# USB_HUB.net
KiCad netlist of a schematic drawn in Altium Designer
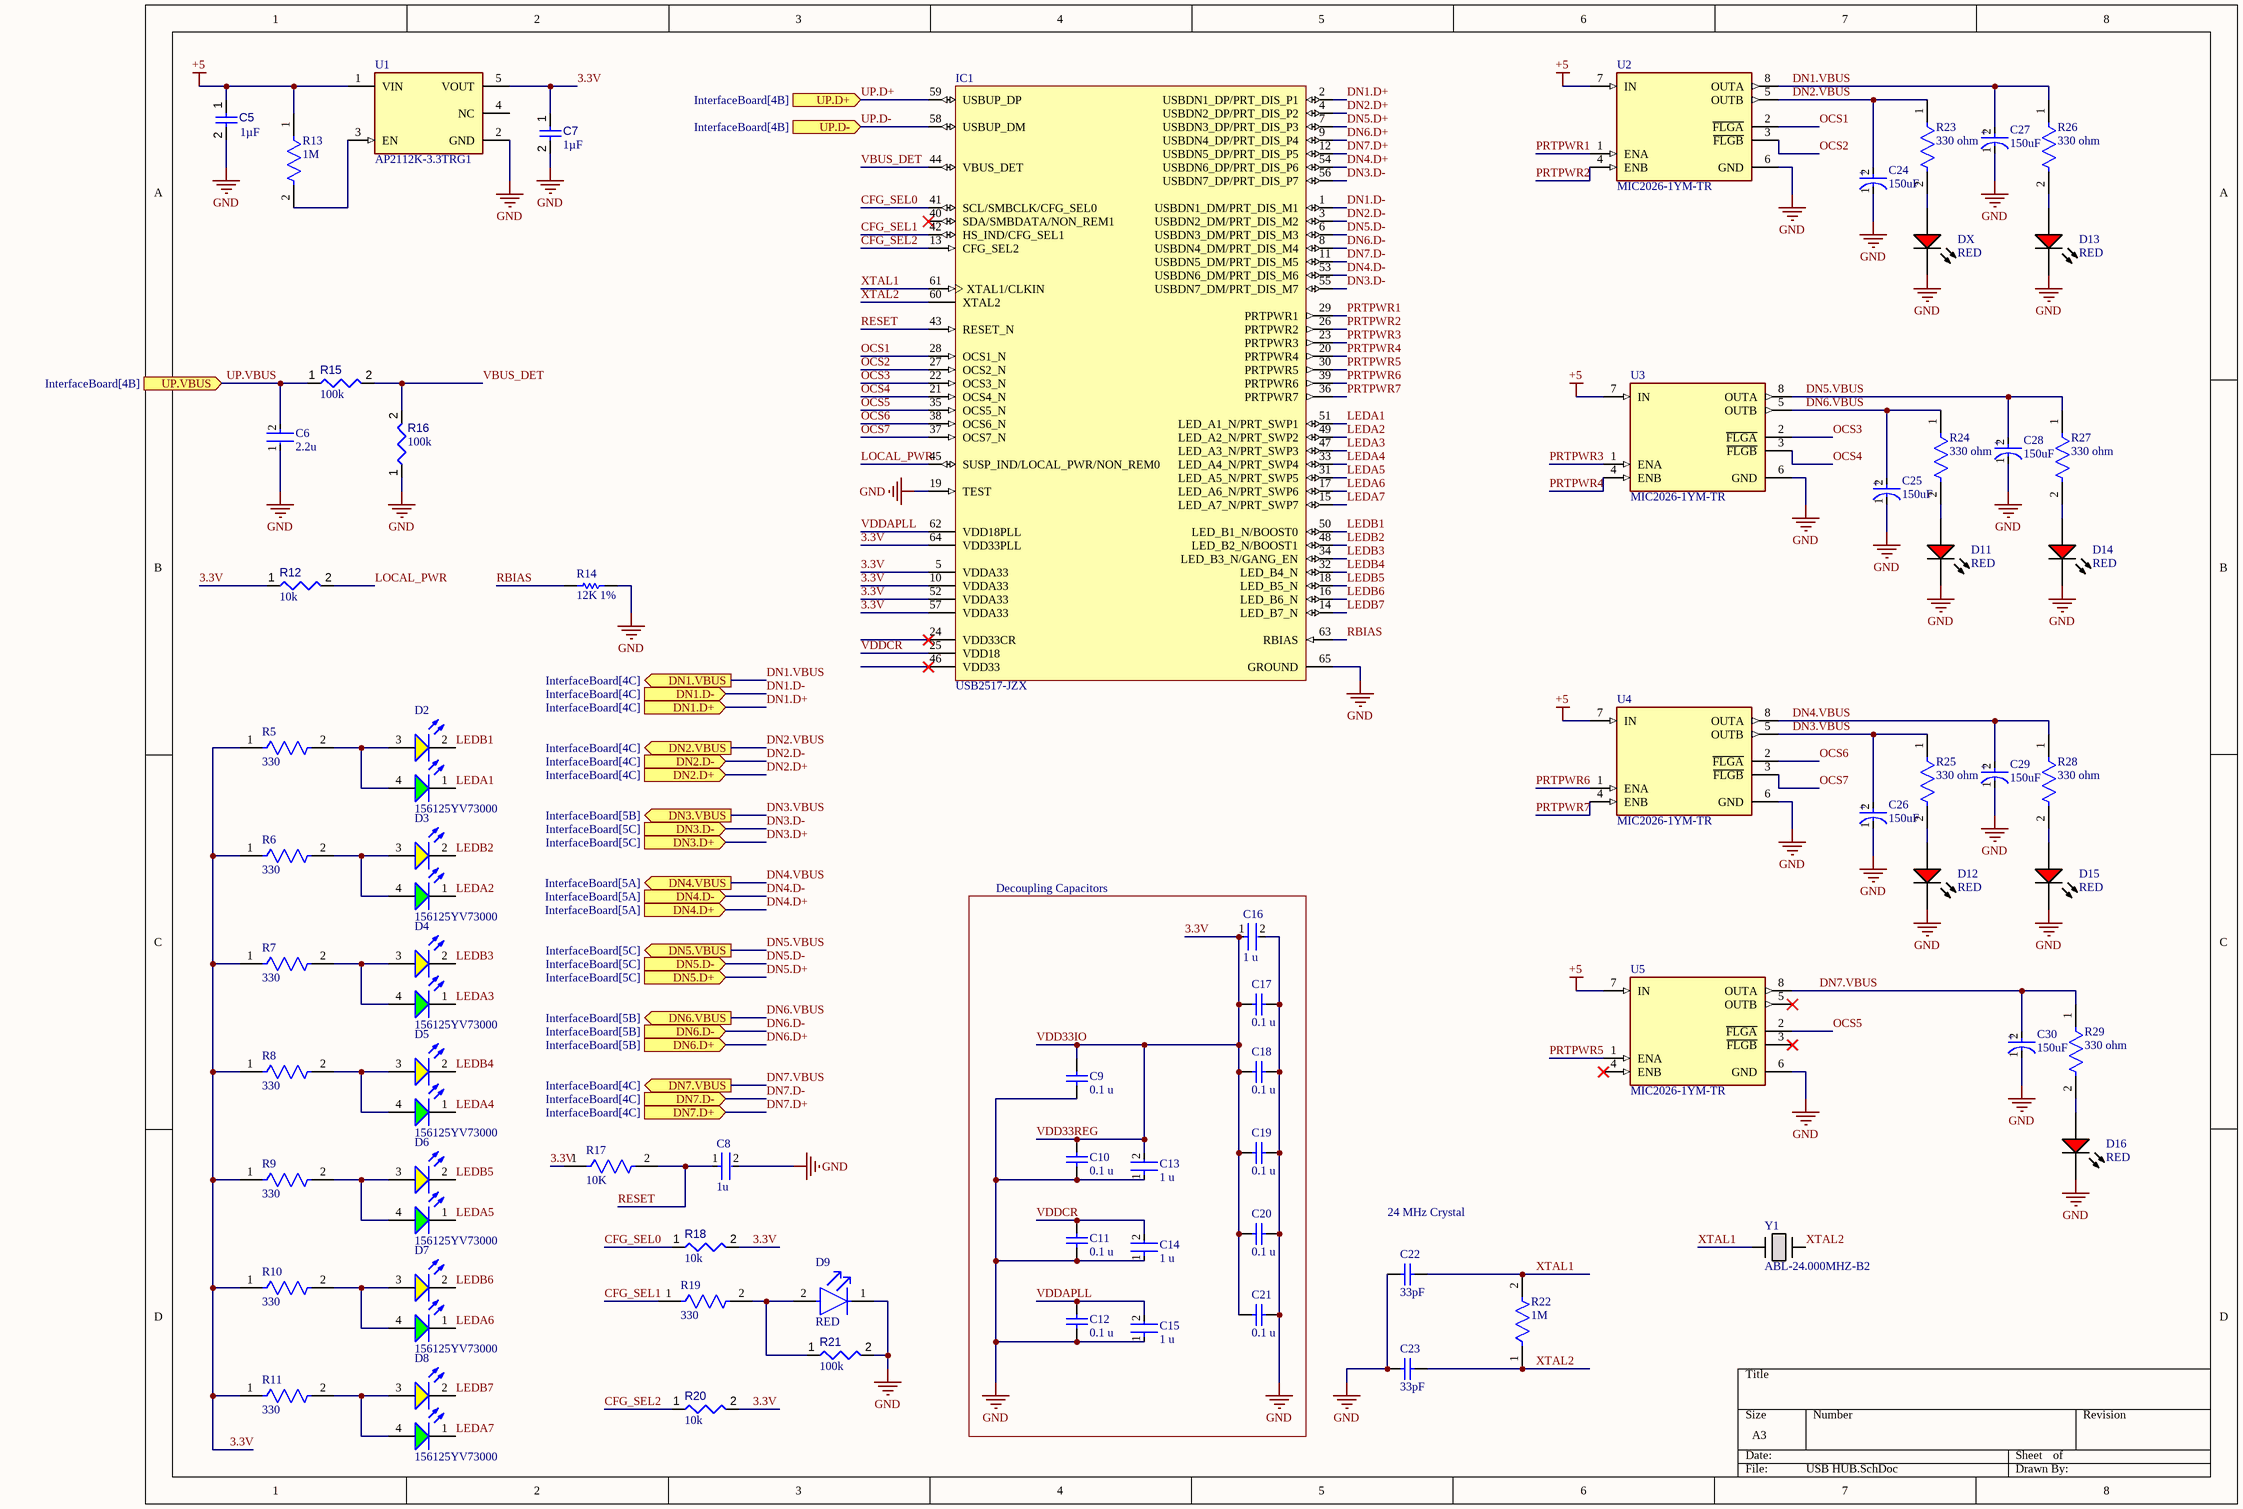
[diagram p0: USB HUB.SchDoc]

(export (version "E")
  (design (tool "Eeschema 10.0.6"))
  (components
    (comp (ref "C5")
      (value "1µF")
      (footprint "CAPC1608X94X35NL15T15")
      (description "Chip Capacitor, 1 uF, +/- 10%, 16 V, 0603 (1608 Metric)")
      (fields (field (name "TOLERANCE") "10%") (field (name "Comment") "Capacitor 1 uF +/- 10% 16 V 0603"))
      (libsource (lib "Isaac Lee Altium Cloud") (part "CAP-NP-2"))
    )
    (comp (ref "C6")
      (value "2.2u")
      (footprint "FP-C1608-080-0_1-MFG")
      (description "Multilayer Ceramic Capacitors 2.2μF ±10% 25V X5R SMD 0603")
      (fields (field (name "TOLERANCE") "10%"))
      (libsource (lib "Altium Content Vault") (part "236180d848d6139a670b325ea6854c9"))
    )
    (comp (ref "C7")
      (value "1µF")
      (footprint "CAPC1608X94X35NL15T15")
      (description "Chip Capacitor, 1 uF, +/- 10%, 16 V, 0603 (1608 Metric)")
      (fields (field (name "TOLERANCE") "10%") (field (name "Comment") "Capacitor 1 uF +/- 10% 16 V 0603"))
      (libsource (lib "Isaac Lee Altium Cloud") (part "CAP-NP-2"))
    )
    (comp (ref "C8")
      (value "1u")
      (footprint "FP-0603-L_1_6_0_15-W_0_81-IPC_A")
      (description "General Purpose Ceramic Capacitor, 0603, 1uF, 10%, X5R, 15%, 6.3V")
      (fields (field (name "VOLTAGE") "6.3V") (field (name "TOLERANCE") "10%"))
      (libsource (lib "Altium Content Vault") (part "02cd4be3c70576c341d710602a673aa"))
    )
    (comp (ref "C9")
      (value "0.1 u")
      (footprint "CAPC1608X90X35LL15T15")
      (description "06035C104KAT4A")
      (fields (field (name "MANUFACTURER") "AVX Interconnect / Elco"))
      (libsource (lib "Altium Content Vault") (part "CAP"))
    )
    (comp (ref "C10")
      (value "0.1 u")
      (footprint "CAPC1608X90X35LL15T15")
      (description "06035C104KAT4A")
      (fields (field (name "MANUFACTURER") "AVX Interconnect / Elco"))
      (libsource (lib "Altium Content Vault") (part "CAP"))
    )
    (comp (ref "C11")
      (value "0.1 u")
      (footprint "CAPC1608X90X35LL15T15")
      (description "06035C104KAT4A")
      (fields (field (name "MANUFACTURER") "AVX Interconnect / Elco"))
      (libsource (lib "Altium Content Vault") (part "CAP"))
    )
    (comp (ref "C12")
      (value "0.1 u")
      (footprint "CAPC1608X90X35LL15T15")
      (description "06035C104KAT4A")
      (fields (field (name "MANUFACTURER") "AVX Interconnect / Elco"))
      (libsource (lib "Altium Content Vault") (part "CAP"))
    )
    (comp (ref "C13")
      (value "1 u")
      (footprint "FP-0603-L_1_6_0_15-W_0_8-IPC_C")
      (description "Ceramic Capacitor General Use 1uF ±10% 50V X7R 0603\r\nUMK107AB7105KA-T")
      (fields (field (name "TOLERANCE") "10%"))
      (libsource (lib "Altium Content Vault") (part "11868f565c42a9108669ba33697ecf6"))
    )
    (comp (ref "C14")
      (value "1 u")
      (footprint "FP-0603-L_1_6_0_15-W_0_8-IPC_C")
      (description "Ceramic Capacitor General Use 1uF ±10% 50V X7R 0603\r\nUMK107AB7105KA-T")
      (fields (field (name "TOLERANCE") "10%"))
      (libsource (lib "Altium Content Vault") (part "11868f565c42a9108669ba33697ecf6"))
    )
    (comp (ref "C15")
      (value "1 u")
      (footprint "FP-0603-L_1_6_0_15-W_0_8-IPC_C")
      (description "Ceramic Capacitor General Use 1uF ±10% 50V X7R 0603\r\nUMK107AB7105KA-T")
      (fields (field (name "TOLERANCE") "10%"))
      (libsource (lib "Altium Content Vault") (part "11868f565c42a9108669ba33697ecf6"))
    )
    (comp (ref "C16")
      (value "1 u")
      (footprint "FP-0603-L_1_6_0_15-W_0_8-IPC_C")
      (description "Ceramic Capacitor General Use 1uF ±10% 50V X7R 0603\r\nUMK107AB7105KA-T")
      (fields (field (name "TOLERANCE") "10%"))
      (libsource (lib "Altium Content Vault") (part "11868f565c42a9108669ba33697ecf6"))
    )
    (comp (ref "C17")
      (value "0.1 u")
      (footprint "CAPC1608X90X35LL15T15")
      (description "06035C104KAT4A")
      (fields (field (name "MANUFACTURER") "AVX Interconnect / Elco"))
      (libsource (lib "Altium Content Vault") (part "CAP"))
    )
    (comp (ref "C18")
      (value "0.1 u")
      (footprint "CAPC1608X90X35LL15T15")
      (description "06035C104KAT4A")
      (fields (field (name "MANUFACTURER") "AVX Interconnect / Elco"))
      (libsource (lib "Altium Content Vault") (part "CAP"))
    )
    (comp (ref "C19")
      (value "0.1 u")
      (footprint "CAPC1608X90X35LL15T15")
      (description "06035C104KAT4A")
      (fields (field (name "MANUFACTURER") "AVX Interconnect / Elco"))
      (libsource (lib "Altium Content Vault") (part "CAP"))
    )
    (comp (ref "C20")
      (value "0.1 u")
      (footprint "CAPC1608X90X35LL15T15")
      (description "06035C104KAT4A")
      (fields (field (name "MANUFACTURER") "AVX Interconnect / Elco"))
      (libsource (lib "Altium Content Vault") (part "CAP"))
    )
    (comp (ref "C21")
      (value "0.1 u")
      (footprint "CAPC1608X90X35LL15T15")
      (description "06035C104KAT4A")
      (fields (field (name "MANUFACTURER") "AVX Interconnect / Elco"))
      (libsource (lib "Altium Content Vault") (part "CAP"))
    )
    (comp (ref "C22")
      (value "33pF")
      (footprint "WCAP-CSGP_0603_L1.6W0.8H0.8_Reflow")
      (description "Ceramic Capacitor 33pF, 16VDC, 0603, ±5 %")
      (fields (field (name "TOLERANCE") "5%"))
      (libsource (lib "Altium Content Vault") (part "Capacitor_Non-Polarized"))
    )
    (comp (ref "C23")
      (value "33pF")
      (footprint "WCAP-CSGP_0603_L1.6W0.8H0.8_Reflow")
      (description "Ceramic Capacitor 33pF, 16VDC, 0603, ±5 %")
      (fields (field (name "TOLERANCE") "5%"))
      (libsource (lib "Altium Content Vault") (part "Capacitor_Non-Polarized"))
    )
    (comp (ref "C24")
      (value "150uF")
      (footprint "FP-OS-CON-SMT-B6-MFG")
      (description "Conductive Polymer Aluminum Solid Capacitors (OS-CON) 150uF ±20% 6.3V")
      (fields (field (name "TOLERANCE") "20%") (field (name "VOLTAGE") "6.3V"))
      (libsource (lib "Altium Content Vault") (part "a00bbbee19879c290e62620ae7e47b1"))
    )
    (comp (ref "C25")
      (value "150uF")
      (footprint "FP-OS-CON-SMT-B6-MFG")
      (description "Conductive Polymer Aluminum Solid Capacitors (OS-CON) 150uF ±20% 6.3V")
      (fields (field (name "TOLERANCE") "20%") (field (name "VOLTAGE") "6.3V"))
      (libsource (lib "Altium Content Vault") (part "a00bbbee19879c290e62620ae7e47b1"))
    )
    (comp (ref "C26")
      (value "150uF")
      (footprint "FP-OS-CON-SMT-B6-MFG")
      (description "Conductive Polymer Aluminum Solid Capacitors (OS-CON) 150uF ±20% 6.3V")
      (fields (field (name "TOLERANCE") "20%") (field (name "VOLTAGE") "6.3V"))
      (libsource (lib "Altium Content Vault") (part "a00bbbee19879c290e62620ae7e47b1"))
    )
    (comp (ref "C27")
      (value "150uF")
      (footprint "FP-OS-CON-SMT-B6-MFG")
      (description "Conductive Polymer Aluminum Solid Capacitors (OS-CON) 150uF ±20% 6.3V")
      (fields (field (name "TOLERANCE") "20%") (field (name "VOLTAGE") "6.3V"))
      (libsource (lib "Altium Content Vault") (part "a00bbbee19879c290e62620ae7e47b1"))
    )
    (comp (ref "C28")
      (value "150uF")
      (footprint "FP-OS-CON-SMT-B6-MFG")
      (description "Conductive Polymer Aluminum Solid Capacitors (OS-CON) 150uF ±20% 6.3V")
      (fields (field (name "TOLERANCE") "20%") (field (name "VOLTAGE") "6.3V"))
      (libsource (lib "Altium Content Vault") (part "a00bbbee19879c290e62620ae7e47b1"))
    )
    (comp (ref "C29")
      (value "150uF")
      (footprint "FP-OS-CON-SMT-B6-MFG")
      (description "Conductive Polymer Aluminum Solid Capacitors (OS-CON) 150uF ±20% 6.3V")
      (fields (field (name "TOLERANCE") "20%") (field (name "VOLTAGE") "6.3V"))
      (libsource (lib "Altium Content Vault") (part "a00bbbee19879c290e62620ae7e47b1"))
    )
    (comp (ref "C30")
      (value "150uF")
      (footprint "FP-OS-CON-SMT-B6-MFG")
      (description "Conductive Polymer Aluminum Solid Capacitors (OS-CON) 150uF ±20% 6.3V")
      (fields (field (name "TOLERANCE") "20%") (field (name "VOLTAGE") "6.3V"))
      (libsource (lib "Altium Content Vault") (part "a00bbbee19879c290e62620ae7e47b1"))
    )
    (comp (ref "D2")
      (value "156125YV73000")
      (footprint "WL-SBRW_1205_reverse mount")
      (description "156125YV73000 Dual Color LED, Yellow/bright Green, Water Clear, 1.2mm")
      (libsource (lib "Altium Content Vault") (part "WL-SBRW_Yellow & Green"))
    )
    (comp (ref "D3")
      (value "156125YV73000")
      (footprint "WL-SBRW_1205_reverse mount")
      (description "156125YV73000 Dual Color LED, Yellow/bright Green, Water Clear, 1.2mm")
      (libsource (lib "Altium Content Vault") (part "WL-SBRW_Yellow & Green"))
    )
    (comp (ref "D4")
      (value "156125YV73000")
      (footprint "WL-SBRW_1205_reverse mount")
      (description "156125YV73000 Dual Color LED, Yellow/bright Green, Water Clear, 1.2mm")
      (libsource (lib "Altium Content Vault") (part "WL-SBRW_Yellow & Green"))
    )
    (comp (ref "D5")
      (value "156125YV73000")
      (footprint "WL-SBRW_1205_reverse mount")
      (description "156125YV73000 Dual Color LED, Yellow/bright Green, Water Clear, 1.2mm")
      (libsource (lib "Altium Content Vault") (part "WL-SBRW_Yellow & Green"))
    )
    (comp (ref "D6")
      (value "156125YV73000")
      (footprint "WL-SBRW_1205_reverse mount")
      (description "156125YV73000 Dual Color LED, Yellow/bright Green, Water Clear, 1.2mm")
      (libsource (lib "Altium Content Vault") (part "WL-SBRW_Yellow & Green"))
    )
    (comp (ref "D7")
      (value "156125YV73000")
      (footprint "WL-SBRW_1205_reverse mount")
      (description "156125YV73000 Dual Color LED, Yellow/bright Green, Water Clear, 1.2mm")
      (libsource (lib "Altium Content Vault") (part "WL-SBRW_Yellow & Green"))
    )
    (comp (ref "D8")
      (value "156125YV73000")
      (footprint "WL-SBRW_1205_reverse mount")
      (description "156125YV73000 Dual Color LED, Yellow/bright Green, Water Clear, 1.2mm")
      (libsource (lib "Altium Content Vault") (part "WL-SBRW_Yellow & Green"))
    )
    (comp (ref "D9")
      (value "RED")
      (footprint "FP-SML-LX0603SIW-TR-MFG")
      (description "LED RED DIFFUSED SMD")
      (libsource (lib "Altium Content Vault") (part "8706943c75ba83719d021d2fdc84c58"))
    )
    (comp (ref "D11")
      (value "RED")
      (footprint "LTST-C191KRKT_V")
      (description "LED Uni-Color Red, 62.5 mW, 25 mA, -30 to 85 degC, 2-Pin SMD, RoHS, Tape and Reel")
      (fields (field (name "POWER") "75mW") (field (name "MANUFACTURER") "Lite-On"))
      (libsource (lib "Isaac Lee Altium Cloud") (part "LED-RED-AK-2"))
    )
    (comp (ref "D12")
      (value "RED")
      (footprint "LTST-C191KRKT_V")
      (description "LED Uni-Color Red, 62.5 mW, 25 mA, -30 to 85 degC, 2-Pin SMD, RoHS, Tape and Reel")
      (fields (field (name "POWER") "75mW") (field (name "MANUFACTURER") "Lite-On"))
      (libsource (lib "Isaac Lee Altium Cloud") (part "LED-RED-AK-2"))
    )
    (comp (ref "D13")
      (value "RED")
      (footprint "LTST-C191KRKT_V")
      (description "LED Uni-Color Red, 62.5 mW, 25 mA, -30 to 85 degC, 2-Pin SMD, RoHS, Tape and Reel")
      (fields (field (name "POWER") "75mW") (field (name "MANUFACTURER") "Lite-On"))
      (libsource (lib "Isaac Lee Altium Cloud") (part "LED-RED-AK-2"))
    )
    (comp (ref "D14")
      (value "RED")
      (footprint "LTST-C191KRKT_V")
      (description "LED Uni-Color Red, 62.5 mW, 25 mA, -30 to 85 degC, 2-Pin SMD, RoHS, Tape and Reel")
      (fields (field (name "POWER") "75mW") (field (name "MANUFACTURER") "Lite-On"))
      (libsource (lib "Isaac Lee Altium Cloud") (part "LED-RED-AK-2"))
    )
    (comp (ref "D15")
      (value "RED")
      (footprint "LTST-C191KRKT_V")
      (description "LED Uni-Color Red, 62.5 mW, 25 mA, -30 to 85 degC, 2-Pin SMD, RoHS, Tape and Reel")
      (fields (field (name "POWER") "75mW") (field (name "MANUFACTURER") "Lite-On"))
      (libsource (lib "Isaac Lee Altium Cloud") (part "LED-RED-AK-2"))
    )
    (comp (ref "D16")
      (value "RED")
      (footprint "LTST-C191KRKT_V")
      (description "LED Uni-Color Red, 62.5 mW, 25 mA, -30 to 85 degC, 2-Pin SMD, RoHS, Tape and Reel")
      (fields (field (name "POWER") "75mW") (field (name "MANUFACTURER") "Lite-On"))
      (libsource (lib "Isaac Lee Altium Cloud") (part "LED-RED-AK-2"))
    )
    (comp (ref "DX")
      (value "RED")
      (footprint "LTST-C191KRKT_V")
      (description "LED Uni-Color Red, 62.5 mW, 25 mA, -30 to 85 degC, 2-Pin SMD, RoHS, Tape and Reel")
      (fields (field (name "POWER") "75mW") (field (name "MANUFACTURER") "Lite-On"))
      (libsource (lib "Isaac Lee Altium Cloud") (part "LED-RED-AK-2"))
    )
    (comp (ref "IC1")
      (value "USB2517-JZX")
      (footprint "MCHP-QFN-64-4700X4700TP_L")
      (description "USB 2.0 Hi-Speed 7-Port Hub Controller, 3 to 3.6 V, 0 to 70 degC, 64-Pin QFN, RoHS, Tape and Reel")
      (fields (field (name "MANUFACTURER") "Microchip"))
      (libsource (lib "Altium Content Vault") (part "MCHP-USB2517-QFN-64"))
    )
    (comp (ref "R5")
      (value "330")
      (footprint "FP-CRGCQ0603-IPC_C")
      (description "CRGCQ 0603 330R 5%")
      (fields
        (field (name "OCTOPART") "https://octopart.com/crgcq0603j330r-te+connectivity-91018118")
        (field (name "MANUFACTURER") "TE Connectivity")
      )
      (libsource (lib "Altium Content Vault") (part "1029c3af85768c4190bb7ad29bc67b5"))
    )
    (comp (ref "R6")
      (value "330")
      (footprint "FP-CRGCQ0603-IPC_C")
      (description "CRGCQ 0603 330R 5%")
      (fields
        (field (name "OCTOPART") "https://octopart.com/crgcq0603j330r-te+connectivity-91018118")
        (field (name "MANUFACTURER") "TE Connectivity")
      )
      (libsource (lib "Altium Content Vault") (part "1029c3af85768c4190bb7ad29bc67b5"))
    )
    (comp (ref "R7")
      (value "330")
      (footprint "FP-CRGCQ0603-IPC_C")
      (description "CRGCQ 0603 330R 5%")
      (fields
        (field (name "OCTOPART") "https://octopart.com/crgcq0603j330r-te+connectivity-91018118")
        (field (name "MANUFACTURER") "TE Connectivity")
      )
      (libsource (lib "Altium Content Vault") (part "1029c3af85768c4190bb7ad29bc67b5"))
    )
    (comp (ref "R8")
      (value "330")
      (footprint "FP-CRGCQ0603-IPC_C")
      (description "CRGCQ 0603 330R 5%")
      (fields
        (field (name "OCTOPART") "https://octopart.com/crgcq0603j330r-te+connectivity-91018118")
        (field (name "MANUFACTURER") "TE Connectivity")
      )
      (libsource (lib "Altium Content Vault") (part "1029c3af85768c4190bb7ad29bc67b5"))
    )
    (comp (ref "R9")
      (value "330")
      (footprint "FP-CRGCQ0603-IPC_C")
      (description "CRGCQ 0603 330R 5%")
      (fields
        (field (name "OCTOPART") "https://octopart.com/crgcq0603j330r-te+connectivity-91018118")
        (field (name "MANUFACTURER") "TE Connectivity")
      )
      (libsource (lib "Altium Content Vault") (part "1029c3af85768c4190bb7ad29bc67b5"))
    )
    (comp (ref "R10")
      (value "330")
      (footprint "FP-CRGCQ0603-IPC_C")
      (description "CRGCQ 0603 330R 5%")
      (fields
        (field (name "OCTOPART") "https://octopart.com/crgcq0603j330r-te+connectivity-91018118")
        (field (name "MANUFACTURER") "TE Connectivity")
      )
      (libsource (lib "Altium Content Vault") (part "1029c3af85768c4190bb7ad29bc67b5"))
    )
    (comp (ref "R11")
      (value "330")
      (footprint "FP-CRGCQ0603-IPC_C")
      (description "CRGCQ 0603 330R 5%")
      (fields
        (field (name "OCTOPART") "https://octopart.com/crgcq0603j330r-te+connectivity-91018118")
        (field (name "MANUFACTURER") "TE Connectivity")
      )
      (libsource (lib "Altium Content Vault") (part "1029c3af85768c4190bb7ad29bc67b5"))
    )
    (comp (ref "R12")
      (value "10k")
      (footprint "RESC1608X55X25ML10T15")
      (description "Chip Resistor, 10 KOhm, +/- 1%, 01 W, -55 to 155 degC, 0603 (1608 Metric)")
      (fields (field (name "POWER") "100mW") (field (name "TOLERANCE") "1%"))
      (libsource (lib "Isaac Lee Altium Cloud") (part "RES-2"))
    )
    (comp (ref "R13")
      (value "1M")
      (footprint "FP-AC0603-IPC_A")
      (description "RES 1MΩ 1.00% 0.1W 0603")
      (fields (field (name "TOLERANCE") "1%"))
      (libsource (lib "Altium Content Vault") (part "1029c3af85768c4190bb7ad29bc67b5"))
    )
    (comp (ref "R14")
      (value "12K 1%")
      (footprint "RESC1608X55X25LL10T15")
      (fields (field (name "MANUFACTURER") "Yageo") (field (name "PART NUMBER") "RC0603FR-1312KL"))
      (libsource (lib "Altium Content Vault") (part "RES"))
    )
    (comp (ref "R15")
      (value "100k")
      (footprint "RESC1608X55X25ML10T15")
      (description "Chip Resistor, 100 KOhm, +/- 1%, 0.1 W, -55 to 155 degC, 0603 (1608 Metric)")
      (fields (field (name "TOLERANCE") "1%") (field (name "POWER") "100mW"))
      (libsource (lib "Isaac Lee Altium Cloud") (part "RES-2"))
    )
    (comp (ref "R16")
      (value "100k")
      (footprint "RESC1608X55X25ML10T15")
      (description "Chip Resistor, 100 KOhm, +/- 1%, 0.1 W, -55 to 155 degC, 0603 (1608 Metric)")
      (fields (field (name "TOLERANCE") "1%") (field (name "POWER") "100mW"))
      (libsource (lib "Isaac Lee Altium Cloud") (part "RES-2"))
    )
    (comp (ref "R17")
      (value "10K")
      (footprint "FP-CRGCQ0603-IPC_C")
      (description "CRGCQ 0603 10K 5%")
      (fields
        (field (name "TOLERANCE") "0.05")
        (field (name "OCTOPART") "https://octopart.com/crgcq0603j10k-te+connectivity-91018097")
      )
      (libsource (lib "Altium Content Vault") (part "1029c3af85768c4190bb7ad29bc67b5"))
    )
    (comp (ref "R18")
      (value "10k")
      (footprint "RESC1608X55X25ML10T15")
      (description "Chip Resistor, 10 KOhm, +/- 1%, 01 W, -55 to 155 degC, 0603 (1608 Metric)")
      (fields (field (name "POWER") "100mW") (field (name "TOLERANCE") "1%"))
      (libsource (lib "Isaac Lee Altium Cloud") (part "RES-2"))
    )
    (comp (ref "R19")
      (value "330")
      (footprint "FP-CRGCQ0603-IPC_C")
      (description "CRGCQ 0603 330R 5%")
      (fields
        (field (name "OCTOPART") "https://octopart.com/crgcq0603j330r-te+connectivity-91018118")
        (field (name "MANUFACTURER") "TE Connectivity")
      )
      (libsource (lib "Altium Content Vault") (part "1029c3af85768c4190bb7ad29bc67b5"))
    )
    (comp (ref "R20")
      (value "10k")
      (footprint "RESC1608X55X25ML10T15")
      (description "Chip Resistor, 10 KOhm, +/- 1%, 01 W, -55 to 155 degC, 0603 (1608 Metric)")
      (fields (field (name "POWER") "100mW") (field (name "TOLERANCE") "1%"))
      (libsource (lib "Isaac Lee Altium Cloud") (part "RES-2"))
    )
    (comp (ref "R21")
      (value "100k")
      (footprint "RESC1608X55X25ML10T15")
      (description "Chip Resistor, 100 KOhm, +/- 1%, 0.1 W, -55 to 155 degC, 0603 (1608 Metric)")
      (fields (field (name "TOLERANCE") "1%") (field (name "POWER") "100mW"))
      (libsource (lib "Isaac Lee Altium Cloud") (part "RES-2"))
    )
    (comp (ref "R22")
      (value "1M")
      (footprint "FP-CRGP0603-IPC_C")
      (description "RES 1M OHM 1% 1/4W 0603")
      (fields (field (name "TOLERANCE") "1%"))
      (libsource (lib "Altium Content Vault") (part "1029c3af85768c4190bb7ad29bc67b5"))
    )
    (comp (ref "R23")
      (value "330 ohm")
      (footprint "FP-MCT0603-MFG")
      (description "RES SMD 100 OHM 1% 1/8W 0603")
      (fields (field (name "TOLERANCE") "0.5%"))
      (libsource (lib "Altium Content Vault") (part "1029c3af85768c4190bb7ad29bc67b5"))
    )
    (comp (ref "R24")
      (value "330 ohm")
      (footprint "FP-MCT0603-MFG")
      (description "RES SMD 100 OHM 1% 1/8W 0603")
      (fields (field (name "TOLERANCE") "0.5%"))
      (libsource (lib "Altium Content Vault") (part "1029c3af85768c4190bb7ad29bc67b5"))
    )
    (comp (ref "R25")
      (value "330 ohm")
      (footprint "FP-MCT0603-MFG")
      (description "RES SMD 100 OHM 1% 1/8W 0603")
      (fields (field (name "TOLERANCE") "0.5%"))
      (libsource (lib "Altium Content Vault") (part "1029c3af85768c4190bb7ad29bc67b5"))
    )
    (comp (ref "R26")
      (value "330 ohm")
      (footprint "FP-MCT0603-MFG")
      (description "RES SMD 100 OHM 1% 1/8W 0603")
      (fields (field (name "TOLERANCE") "0.5%"))
      (libsource (lib "Altium Content Vault") (part "1029c3af85768c4190bb7ad29bc67b5"))
    )
    (comp (ref "R27")
      (value "330 ohm")
      (footprint "FP-MCT0603-MFG")
      (description "RES SMD 100 OHM 1% 1/8W 0603")
      (fields (field (name "TOLERANCE") "0.5%"))
      (libsource (lib "Altium Content Vault") (part "1029c3af85768c4190bb7ad29bc67b5"))
    )
    (comp (ref "R28")
      (value "330 ohm")
      (footprint "FP-MCT0603-MFG")
      (description "RES SMD 100 OHM 1% 1/8W 0603")
      (fields (field (name "TOLERANCE") "0.5%"))
      (libsource (lib "Altium Content Vault") (part "1029c3af85768c4190bb7ad29bc67b5"))
    )
    (comp (ref "R29")
      (value "330 ohm")
      (footprint "FP-MCT0603-MFG")
      (description "RES SMD 100 OHM 1% 1/8W 0603")
      (fields (field (name "TOLERANCE") "0.5%"))
      (libsource (lib "Altium Content Vault") (part "1029c3af85768c4190bb7ad29bc67b5"))
    )
    (comp (ref "U1")
      (value "AP2112K-3.3TRG1")
      (footprint "FP-SOT25-IPC_A")
      (description "IC REG LINEAR 3.3V 600MA SOT25")
      (libsource (lib "Altium Content Vault") (part "c8ab751aee5229183125ab046a11caa"))
    )
    (comp (ref "U2")
      (value "MIC2026-1YM-TR")
      (footprint "FP-SOICN-8LD-PL-1-IPC_B")
      (description "IC PWR SWITCH N-CHAN 1:2 8SOIC")
      (libsource (lib "Altium Content Vault") (part "2199806be52ea882e5e452ced29a7fe"))
    )
    (comp (ref "U3")
      (value "MIC2026-1YM-TR")
      (footprint "FP-SOICN-8LD-PL-1-IPC_B")
      (description "IC PWR SWITCH N-CHAN 1:2 8SOIC")
      (libsource (lib "Altium Content Vault") (part "2199806be52ea882e5e452ced29a7fe"))
    )
    (comp (ref "U4")
      (value "MIC2026-1YM-TR")
      (footprint "FP-SOICN-8LD-PL-1-IPC_B")
      (description "IC PWR SWITCH N-CHAN 1:2 8SOIC")
      (libsource (lib "Altium Content Vault") (part "2199806be52ea882e5e452ced29a7fe"))
    )
    (comp (ref "U5")
      (value "MIC2026-1YM-TR")
      (footprint "FP-SOICN-8LD-PL-1-IPC_B")
      (description "IC PWR SWITCH N-CHAN 1:2 8SOIC")
      (libsource (lib "Altium Content Vault") (part "2199806be52ea882e5e452ced29a7fe"))
    )
    (comp (ref "Y1")
      (value "ABL-24.000MHZ-B2")
      (footprint "XTAL_HC49P488W46L1150T500H350")
      (description "No Description Available")
      (fields (field (name "COPYRIGHT") "Copyright (C) 2025 Ultra Librarian. All rights reserved."))
      (libsource (lib "ABL-24P000MHZ-B2") (part "ABL-24.000MHZ-B2"))
    )
  )
  (nets
    (net (code "1") (name "+5") (class "Default")
      (node (ref "C5") (pin "1") (pinfunction "1_1") (pintype "passive"))
      (node (ref "R13") (pin "1") (pinfunction "1_1") (pintype "passive"))
      (node (ref "U1") (pin "1") (pinfunction "VIN_1") (pintype "power_in"))
      (node (ref "U2") (pin "7") (pinfunction "IN_7") (pintype "input"))
      (node (ref "U3") (pin "7") (pinfunction "IN_7") (pintype "input"))
      (node (ref "U4") (pin "7") (pinfunction "IN_7") (pintype "input"))
      (node (ref "U5") (pin "7") (pinfunction "IN_7") (pintype "input"))
    )
    (net (code "2") (name "/3.3V") (class "Default")
      (node (ref "C10") (pin "1") (pinfunction "1_1") (pintype "passive"))
      (node (ref "C13") (pin "2") (pinfunction "2_2") (pintype "passive"))
      (node (ref "C16") (pin "1") (pinfunction "1_1") (pintype "passive"))
      (node (ref "C17") (pin "2") (pinfunction "2_2") (pintype "passive"))
      (node (ref "C18") (pin "2") (pinfunction "2_2") (pintype "passive"))
      (node (ref "C19") (pin "2") (pinfunction "2_2") (pintype "passive"))
      (node (ref "C20") (pin "2") (pinfunction "2_2") (pintype "passive"))
      (node (ref "C21") (pin "2") (pinfunction "2_2") (pintype "passive"))
      (node (ref "C7") (pin "1") (pinfunction "1_1") (pintype "passive"))
      (node (ref "C9") (pin "1") (pinfunction "1_1") (pintype "passive"))
      (node (ref "IC1") (pin "10") (pinfunction "VDDA33_10") (pintype "power_in"))
      (node (ref "IC1") (pin "5") (pinfunction "VDDA33_5") (pintype "power_in"))
      (node (ref "IC1") (pin "52") (pinfunction "VDDA33_52") (pintype "power_in"))
      (node (ref "IC1") (pin "57") (pinfunction "VDDA33_57") (pintype "power_in"))
      (node (ref "IC1") (pin "64") (pinfunction "VDD33PLL_64") (pintype "power_in"))
      (node (ref "R10") (pin "1") (pinfunction "1_1") (pintype "passive"))
      (node (ref "R11") (pin "1") (pinfunction "1_1") (pintype "passive"))
      (node (ref "R12") (pin "1") (pinfunction "1_1") (pintype "passive"))
      (node (ref "R17") (pin "1") (pinfunction "1_1") (pintype "passive"))
      (node (ref "R18") (pin "2") (pinfunction "2_2") (pintype "passive"))
      (node (ref "R20") (pin "2") (pinfunction "2_2") (pintype "passive"))
      (node (ref "R5") (pin "1") (pinfunction "1_1") (pintype "passive"))
      (node (ref "R6") (pin "1") (pinfunction "1_1") (pintype "passive"))
      (node (ref "R7") (pin "1") (pinfunction "1_1") (pintype "passive"))
      (node (ref "R8") (pin "1") (pinfunction "1_1") (pintype "passive"))
      (node (ref "R9") (pin "1") (pinfunction "1_1") (pintype "passive"))
      (node (ref "U1") (pin "5") (pinfunction "VOUT_5") (pintype "power_in"))
    )
    (net (code "4") (name "/CFG_SEL0") (class "Default")
      (node (ref "IC1") (pin "41") (pinfunction "SCL/SMBCLK/CFG_SEL0_41") (pintype "bidirectional"))
      (node (ref "R18") (pin "1") (pinfunction "1_1") (pintype "passive"))
    )
    (net (code "5") (name "/CFG_SEL1") (class "Default")
      (node (ref "IC1") (pin "42") (pinfunction "HS_IND/CFG_SEL1_42") (pintype "bidirectional"))
      (node (ref "R19") (pin "1") (pinfunction "1_1") (pintype "passive"))
    )
    (net (code "6") (name "/CFG_SEL2") (class "Default")
      (node (ref "IC1") (pin "13") (pinfunction "CFG_SEL2_13") (pintype "input"))
      (node (ref "R20") (pin "1") (pinfunction "1_1") (pintype "passive"))
    )
    (net (code "7") (name "/DN1.D+") (class "Default")
      (node (ref "IC1") (pin "2") (pinfunction "USBDN1_DP/PRT_DIS_P1_2") (pintype "bidirectional"))
    )
    (net (code "8") (name "/DN1.D-") (class "Default")
      (node (ref "IC1") (pin "1") (pinfunction "USBDN1_DM/PRT_DIS_M1_1") (pintype "bidirectional"))
    )
    (net (code "9") (name "/DN1.VBUS") (class "Default")
      (node (ref "C27") (pin "2") (pinfunction "A_2") (pintype "passive"))
      (node (ref "R26") (pin "1") (pinfunction "1_1") (pintype "passive"))
      (node (ref "U2") (pin "8") (pinfunction "OUTA_8") (pintype "output"))
    )
    (net (code "10") (name "/DN2.D+") (class "Default")
      (node (ref "IC1") (pin "4") (pinfunction "USBDN2_DP/PRT_DIS_P2_4") (pintype "bidirectional"))
    )
    (net (code "11") (name "/DN2.D-") (class "Default")
      (node (ref "IC1") (pin "3") (pinfunction "USBDN2_DM/PRT_DIS_M2_3") (pintype "bidirectional"))
    )
    (net (code "12") (name "/DN2.VBUS") (class "Default")
      (node (ref "C24") (pin "2") (pinfunction "A_2") (pintype "passive"))
      (node (ref "R23") (pin "1") (pinfunction "1_1") (pintype "passive"))
      (node (ref "U2") (pin "5") (pinfunction "OUTB_5") (pintype "output"))
    )
    (net (code "14") (name "/DN3.D-") (class "Default")
      (node (ref "IC1") (pin "55") (pinfunction "USBDN7_DM/PRT_DIS_M7_55") (pintype "bidirectional"))
      (node (ref "IC1") (pin "56") (pinfunction "USBDN7_DP/PRT_DIS_P7_56") (pintype "bidirectional"))
    )
    (net (code "15") (name "/DN3.VBUS") (class "Default")
      (node (ref "C26") (pin "2") (pinfunction "A_2") (pintype "passive"))
      (node (ref "R25") (pin "1") (pinfunction "1_1") (pintype "passive"))
      (node (ref "U4") (pin "5") (pinfunction "OUTB_5") (pintype "output"))
    )
    (net (code "16") (name "/DN4.D+") (class "Default")
      (node (ref "IC1") (pin "54") (pinfunction "USBDN6_DP/PRT_DIS_P6_54") (pintype "bidirectional"))
    )
    (net (code "17") (name "/DN4.D-") (class "Default")
      (node (ref "IC1") (pin "53") (pinfunction "USBDN6_DM/PRT_DIS_M6_53") (pintype "bidirectional"))
    )
    (net (code "18") (name "/DN4.VBUS") (class "Default")
      (node (ref "C29") (pin "2") (pinfunction "A_2") (pintype "passive"))
      (node (ref "R28") (pin "1") (pinfunction "1_1") (pintype "passive"))
      (node (ref "U4") (pin "8") (pinfunction "OUTA_8") (pintype "output"))
    )
    (net (code "19") (name "/DN5.D+") (class "Default")
      (node (ref "IC1") (pin "7") (pinfunction "USBDN3_DP/PRT_DIS_P3_7") (pintype "bidirectional"))
    )
    (net (code "20") (name "/DN5.D-") (class "Default")
      (node (ref "IC1") (pin "6") (pinfunction "USBDN3_DM/PRT_DIS_M3_6") (pintype "bidirectional"))
    )
    (net (code "21") (name "/DN5.VBUS") (class "Default")
      (node (ref "C28") (pin "2") (pinfunction "A_2") (pintype "passive"))
      (node (ref "R27") (pin "1") (pinfunction "1_1") (pintype "passive"))
      (node (ref "U3") (pin "8") (pinfunction "OUTA_8") (pintype "output"))
    )
    (net (code "22") (name "/DN6.D+") (class "Default")
      (node (ref "IC1") (pin "9") (pinfunction "USBDN4_DP/PRT_DIS_P4_9") (pintype "bidirectional"))
    )
    (net (code "23") (name "/DN6.D-") (class "Default")
      (node (ref "IC1") (pin "8") (pinfunction "USBDN4_DM/PRT_DIS_M4_8") (pintype "bidirectional"))
    )
    (net (code "24") (name "/DN6.VBUS") (class "Default")
      (node (ref "C25") (pin "2") (pinfunction "A_2") (pintype "passive"))
      (node (ref "R24") (pin "1") (pinfunction "1_1") (pintype "passive"))
      (node (ref "U3") (pin "5") (pinfunction "OUTB_5") (pintype "output"))
    )
    (net (code "25") (name "/DN7.D+") (class "Default")
      (node (ref "IC1") (pin "12") (pinfunction "USBDN5_DP/PRT_DIS_P5_12") (pintype "bidirectional"))
    )
    (net (code "26") (name "/DN7.D-") (class "Default")
      (node (ref "IC1") (pin "11") (pinfunction "USBDN5_DM/PRT_DIS_M5_11") (pintype "bidirectional"))
    )
    (net (code "27") (name "/DN7.VBUS") (class "Default")
      (node (ref "C30") (pin "2") (pinfunction "A_2") (pintype "passive"))
      (node (ref "R29") (pin "1") (pinfunction "1_1") (pintype "passive"))
      (node (ref "U5") (pin "8") (pinfunction "OUTA_8") (pintype "output"))
    )
    (net (code "28") (name "/LEDA1") (class "Default")
      (node (ref "D2") (pin "1") (pinfunction "K_1") (pintype "passive"))
      (node (ref "IC1") (pin "51") (pinfunction "LED_A1_N/PRT_SWP1_51") (pintype "bidirectional"))
    )
    (net (code "29") (name "/LEDA2") (class "Default")
      (node (ref "D3") (pin "1") (pinfunction "K_1") (pintype "passive"))
      (node (ref "IC1") (pin "49") (pinfunction "LED_A2_N/PRT_SWP2_49") (pintype "bidirectional"))
    )
    (net (code "30") (name "/LEDA3") (class "Default")
      (node (ref "D4") (pin "1") (pinfunction "K_1") (pintype "passive"))
      (node (ref "IC1") (pin "47") (pinfunction "LED_A3_N/PRT_SWP3_47") (pintype "bidirectional"))
    )
    (net (code "31") (name "/LEDA4") (class "Default")
      (node (ref "D5") (pin "1") (pinfunction "K_1") (pintype "passive"))
      (node (ref "IC1") (pin "33") (pinfunction "LED_A4_N/PRT_SWP4_33") (pintype "bidirectional"))
    )
    (net (code "32") (name "/LEDA5") (class "Default")
      (node (ref "D6") (pin "1") (pinfunction "K_1") (pintype "passive"))
      (node (ref "IC1") (pin "31") (pinfunction "LED_A5_N/PRT_SWP5_31") (pintype "bidirectional"))
    )
    (net (code "33") (name "/LEDA6") (class "Default")
      (node (ref "D7") (pin "1") (pinfunction "K_1") (pintype "passive"))
      (node (ref "IC1") (pin "17") (pinfunction "LED_A6_N/PRT_SWP6_17") (pintype "bidirectional"))
    )
    (net (code "34") (name "/LEDA7") (class "Default")
      (node (ref "D8") (pin "1") (pinfunction "K_1") (pintype "passive"))
      (node (ref "IC1") (pin "15") (pinfunction "LED_A7_N/PRT_SWP7_15") (pintype "bidirectional"))
    )
    (net (code "35") (name "/LEDB1") (class "Default")
      (node (ref "D2") (pin "2") (pinfunction "K_2") (pintype "passive"))
      (node (ref "IC1") (pin "50") (pinfunction "LED_B1_N/BOOST0_50") (pintype "bidirectional"))
    )
    (net (code "36") (name "/LEDB2") (class "Default")
      (node (ref "D3") (pin "2") (pinfunction "K_2") (pintype "passive"))
      (node (ref "IC1") (pin "48") (pinfunction "LED_B2_N/BOOST1_48") (pintype "bidirectional"))
    )
    (net (code "37") (name "/LEDB3") (class "Default")
      (node (ref "D4") (pin "2") (pinfunction "K_2") (pintype "passive"))
      (node (ref "IC1") (pin "34") (pinfunction "LED_B3_N/GANG_EN_34") (pintype "bidirectional"))
    )
    (net (code "38") (name "/LEDB4") (class "Default")
      (node (ref "D5") (pin "2") (pinfunction "K_2") (pintype "passive"))
      (node (ref "IC1") (pin "32") (pinfunction "LED_B4_N_32") (pintype "bidirectional"))
    )
    (net (code "39") (name "/LEDB5") (class "Default")
      (node (ref "D6") (pin "2") (pinfunction "K_2") (pintype "passive"))
      (node (ref "IC1") (pin "18") (pinfunction "LED_B5_N_18") (pintype "bidirectional"))
    )
    (net (code "40") (name "/LEDB6") (class "Default")
      (node (ref "D7") (pin "2") (pinfunction "K_2") (pintype "passive"))
      (node (ref "IC1") (pin "16") (pinfunction "LED_B6_N_16") (pintype "bidirectional"))
    )
    (net (code "41") (name "/LEDB7") (class "Default")
      (node (ref "D8") (pin "2") (pinfunction "K_2") (pintype "passive"))
      (node (ref "IC1") (pin "14") (pinfunction "LED_B7_N_14") (pintype "bidirectional"))
    )
    (net (code "42") (name "/LOCAL_PWR") (class "Default")
      (node (ref "IC1") (pin "45") (pinfunction "SUSP_IND/LOCAL_PWR/NON_REM0_45") (pintype "bidirectional"))
      (node (ref "R12") (pin "2") (pinfunction "2_2") (pintype "passive"))
    )
    (net (code "43") (name "/OCS1") (class "Default")
      (node (ref "IC1") (pin "28") (pinfunction "OCS1_N_28") (pintype "input"))
      (node (ref "U2") (pin "2") (pinfunction "~{FLGA}_2") (pintype "open_collector"))
    )
    (net (code "44") (name "/OCS2") (class "Default")
      (node (ref "IC1") (pin "27") (pinfunction "OCS2_N_27") (pintype "input"))
      (node (ref "U2") (pin "3") (pinfunction "~{FLGB}_3") (pintype "open_collector"))
    )
    (net (code "45") (name "/OCS3") (class "Default")
      (node (ref "IC1") (pin "22") (pinfunction "OCS3_N_22") (pintype "input"))
      (node (ref "U3") (pin "2") (pinfunction "~{FLGA}_2") (pintype "open_collector"))
    )
    (net (code "46") (name "/OCS4") (class "Default")
      (node (ref "IC1") (pin "21") (pinfunction "OCS4_N_21") (pintype "input"))
      (node (ref "U3") (pin "3") (pinfunction "~{FLGB}_3") (pintype "open_collector"))
    )
    (net (code "47") (name "/OCS5") (class "Default")
      (node (ref "IC1") (pin "35") (pinfunction "OCS5_N_35") (pintype "input"))
      (node (ref "U5") (pin "2") (pinfunction "~{FLGA}_2") (pintype "open_collector"))
    )
    (net (code "48") (name "/OCS6") (class "Default")
      (node (ref "IC1") (pin "38") (pinfunction "OCS6_N_38") (pintype "input"))
      (node (ref "U4") (pin "2") (pinfunction "~{FLGA}_2") (pintype "open_collector"))
    )
    (net (code "49") (name "/OCS7") (class "Default")
      (node (ref "IC1") (pin "37") (pinfunction "OCS7_N_37") (pintype "input"))
      (node (ref "U4") (pin "3") (pinfunction "~{FLGB}_3") (pintype "open_collector"))
    )
    (net (code "50") (name "/PRTPWR1") (class "Default")
      (node (ref "IC1") (pin "29") (pinfunction "PRTPWR1_29") (pintype "output"))
      (node (ref "U2") (pin "1") (pinfunction "ENA_1") (pintype "input"))
    )
    (net (code "51") (name "/PRTPWR2") (class "Default")
      (node (ref "IC1") (pin "26") (pinfunction "PRTPWR2_26") (pintype "output"))
      (node (ref "U2") (pin "4") (pinfunction "ENB_4") (pintype "input"))
    )
    (net (code "52") (name "/PRTPWR3") (class "Default")
      (node (ref "IC1") (pin "23") (pinfunction "PRTPWR3_23") (pintype "output"))
      (node (ref "U3") (pin "1") (pinfunction "ENA_1") (pintype "input"))
    )
    (net (code "53") (name "/PRTPWR4") (class "Default")
      (node (ref "IC1") (pin "20") (pinfunction "PRTPWR4_20") (pintype "output"))
      (node (ref "U3") (pin "4") (pinfunction "ENB_4") (pintype "input"))
    )
    (net (code "54") (name "/PRTPWR5") (class "Default")
      (node (ref "IC1") (pin "30") (pinfunction "PRTPWR5_30") (pintype "output"))
      (node (ref "U5") (pin "1") (pinfunction "ENA_1") (pintype "input"))
    )
    (net (code "55") (name "/PRTPWR6") (class "Default")
      (node (ref "IC1") (pin "39") (pinfunction "PRTPWR6_39") (pintype "output"))
      (node (ref "U4") (pin "1") (pinfunction "ENA_1") (pintype "input"))
    )
    (net (code "56") (name "/PRTPWR7") (class "Default")
      (node (ref "IC1") (pin "36") (pinfunction "PRTPWR7_36") (pintype "output"))
      (node (ref "U4") (pin "4") (pinfunction "ENB_4") (pintype "input"))
    )
    (net (code "57") (name "/RBIAS") (class "Default")
      (node (ref "IC1") (pin "63") (pinfunction "RBIAS_63") (pintype "input"))
      (node (ref "R14") (pin "1") (pinfunction "1_1") (pintype "passive"))
    )
    (net (code "58") (name "/RESET") (class "Default")
      (node (ref "C8") (pin "1") (pinfunction "1_1") (pintype "passive"))
      (node (ref "IC1") (pin "43") (pinfunction "RESET_N_43") (pintype "input"))
      (node (ref "R17") (pin "2") (pinfunction "2_2") (pintype "passive"))
    )
    (net (code "59") (name "/UP.D+") (class "Default")
      (node (ref "IC1") (pin "59") (pinfunction "USBUP_DP_59") (pintype "bidirectional"))
    )
    (net (code "60") (name "/UP.D-") (class "Default")
      (node (ref "IC1") (pin "58") (pinfunction "USBUP_DM_58") (pintype "bidirectional"))
    )
    (net (code "61") (name "/UP.VBUS") (class "Default")
      (node (ref "C6") (pin "2") (pinfunction "2_2") (pintype "passive"))
      (node (ref "R15") (pin "1") (pinfunction "1_1") (pintype "passive"))
    )
    (net (code "62") (name "/VBUS_DET") (class "Default")
      (node (ref "IC1") (pin "44") (pinfunction "VBUS_DET_44") (pintype "bidirectional"))
      (node (ref "R15") (pin "2") (pinfunction "2_2") (pintype "passive"))
      (node (ref "R16") (pin "2") (pinfunction "2_2") (pintype "passive"))
    )
    (net (code "63") (name "/VDDAPLL") (class "Default")
      (node (ref "C12") (pin "1") (pinfunction "1_1") (pintype "passive"))
      (node (ref "C15") (pin "2") (pinfunction "2_2") (pintype "passive"))
      (node (ref "IC1") (pin "62") (pinfunction "VDD18PLL_62") (pintype "power_in"))
    )
    (net (code "64") (name "/VDDCR") (class "Default")
      (node (ref "C11") (pin "1") (pinfunction "1_1") (pintype "passive"))
      (node (ref "C14") (pin "2") (pinfunction "2_2") (pintype "passive"))
      (node (ref "IC1") (pin "25") (pinfunction "VDD18_25") (pintype "power_in"))
    )
    (net (code "65") (name "/XTAL1") (class "Default")
      (node (ref "C22") (pin "2") (pinfunction "2_2") (pintype "passive"))
      (node (ref "IC1") (pin "61") (pinfunction "XTAL1/CLKIN_61") (pintype "input"))
      (node (ref "R22") (pin "2") (pinfunction "2_2") (pintype "passive"))
      (node (ref "Y1") (pin "1") (pinfunction "1_1") (pintype "passive"))
    )
    (net (code "66") (name "/XTAL2") (class "Default")
      (node (ref "C23") (pin "2") (pinfunction "2_2") (pintype "passive"))
      (node (ref "IC1") (pin "60") (pinfunction "XTAL2_60") (pintype "passive"))
      (node (ref "R22") (pin "1") (pinfunction "1_1") (pintype "passive"))
      (node (ref "Y1") (pin "2") (pinfunction "2_2") (pintype "passive"))
    )
    (net (code "67") (name "GND") (class "Default")
      (node (ref "C10") (pin "2") (pinfunction "2_2") (pintype "passive"))
      (node (ref "C11") (pin "2") (pinfunction "2_2") (pintype "passive"))
      (node (ref "C12") (pin "2") (pinfunction "2_2") (pintype "passive"))
      (node (ref "C13") (pin "1") (pinfunction "1_1") (pintype "passive"))
      (node (ref "C14") (pin "1") (pinfunction "1_1") (pintype "passive"))
      (node (ref "C15") (pin "1") (pinfunction "1_1") (pintype "passive"))
      (node (ref "C16") (pin "2") (pinfunction "2_2") (pintype "passive"))
      (node (ref "C17") (pin "1") (pinfunction "1_1") (pintype "passive"))
      (node (ref "C18") (pin "1") (pinfunction "1_1") (pintype "passive"))
      (node (ref "C19") (pin "1") (pinfunction "1_1") (pintype "passive"))
      (node (ref "C20") (pin "1") (pinfunction "1_1") (pintype "passive"))
      (node (ref "C21") (pin "1") (pinfunction "1_1") (pintype "passive"))
      (node (ref "C22") (pin "1") (pinfunction "1_1") (pintype "passive"))
      (node (ref "C23") (pin "1") (pinfunction "1_1") (pintype "passive"))
      (node (ref "C24") (pin "1") (pinfunction "C_1") (pintype "passive"))
      (node (ref "C25") (pin "1") (pinfunction "C_1") (pintype "passive"))
      (node (ref "C26") (pin "1") (pinfunction "C_1") (pintype "passive"))
      (node (ref "C27") (pin "1") (pinfunction "C_1") (pintype "passive"))
      (node (ref "C28") (pin "1") (pinfunction "C_1") (pintype "passive"))
      (node (ref "C29") (pin "1") (pinfunction "C_1") (pintype "passive"))
      (node (ref "C30") (pin "1") (pinfunction "C_1") (pintype "passive"))
      (node (ref "C5") (pin "2") (pinfunction "2_2") (pintype "passive"))
      (node (ref "C6") (pin "1") (pinfunction "1_1") (pintype "passive"))
      (node (ref "C7") (pin "2") (pinfunction "2_2") (pintype "passive"))
      (node (ref "C8") (pin "2") (pinfunction "2_2") (pintype "passive"))
      (node (ref "C9") (pin "2") (pinfunction "2_2") (pintype "passive"))
      (node (ref "D11") (pin "2") (pinfunction "K_2") (pintype "passive"))
      (node (ref "D12") (pin "2") (pinfunction "K_2") (pintype "passive"))
      (node (ref "D13") (pin "2") (pinfunction "K_2") (pintype "passive"))
      (node (ref "D14") (pin "2") (pinfunction "K_2") (pintype "passive"))
      (node (ref "D15") (pin "2") (pinfunction "K_2") (pintype "passive"))
      (node (ref "D16") (pin "2") (pinfunction "K_2") (pintype "passive"))
      (node (ref "D9") (pin "1") (pinfunction "C_1") (pintype "passive"))
      (node (ref "DX") (pin "2") (pinfunction "K_2") (pintype "passive"))
      (node (ref "IC1") (pin "19") (pinfunction "TEST_19") (pintype "input"))
      (node (ref "IC1") (pin "65") (pinfunction "GROUND_65") (pintype "power_in"))
      (node (ref "R14") (pin "2") (pinfunction "2_2") (pintype "passive"))
      (node (ref "R16") (pin "1") (pinfunction "1_1") (pintype "passive"))
      (node (ref "R21") (pin "2") (pinfunction "2_2") (pintype "passive"))
      (node (ref "U1") (pin "2") (pinfunction "GND_2") (pintype "power_in"))
      (node (ref "U2") (pin "6") (pinfunction "GND_6") (pintype "power_in"))
      (node (ref "U3") (pin "6") (pinfunction "GND_6") (pintype "power_in"))
      (node (ref "U4") (pin "6") (pinfunction "GND_6") (pintype "power_in"))
      (node (ref "U5") (pin "6") (pinfunction "GND_6") (pintype "power_in"))
    )
    (net (code "68") (name "Net-(D2-A-Pad3)") (class "Default")
      (node (ref "D2") (pin "3") (pinfunction "A_3") (pintype "passive"))
      (node (ref "D2") (pin "4") (pinfunction "A_4") (pintype "passive"))
      (node (ref "R5") (pin "2") (pinfunction "2_2") (pintype "passive"))
    )
    (net (code "69") (name "Net-(D3-A-Pad3)") (class "Default")
      (node (ref "D3") (pin "3") (pinfunction "A_3") (pintype "passive"))
      (node (ref "D3") (pin "4") (pinfunction "A_4") (pintype "passive"))
      (node (ref "R6") (pin "2") (pinfunction "2_2") (pintype "passive"))
    )
    (net (code "70") (name "Net-(D4-A-Pad3)") (class "Default")
      (node (ref "D4") (pin "3") (pinfunction "A_3") (pintype "passive"))
      (node (ref "D4") (pin "4") (pinfunction "A_4") (pintype "passive"))
      (node (ref "R7") (pin "2") (pinfunction "2_2") (pintype "passive"))
    )
    (net (code "71") (name "Net-(D5-A-Pad3)") (class "Default")
      (node (ref "D5") (pin "3") (pinfunction "A_3") (pintype "passive"))
      (node (ref "D5") (pin "4") (pinfunction "A_4") (pintype "passive"))
      (node (ref "R8") (pin "2") (pinfunction "2_2") (pintype "passive"))
    )
    (net (code "72") (name "Net-(D6-A-Pad3)") (class "Default")
      (node (ref "D6") (pin "3") (pinfunction "A_3") (pintype "passive"))
      (node (ref "D6") (pin "4") (pinfunction "A_4") (pintype "passive"))
      (node (ref "R9") (pin "2") (pinfunction "2_2") (pintype "passive"))
    )
    (net (code "73") (name "Net-(D7-A-Pad3)") (class "Default")
      (node (ref "D7") (pin "3") (pinfunction "A_3") (pintype "passive"))
      (node (ref "D7") (pin "4") (pinfunction "A_4") (pintype "passive"))
      (node (ref "R10") (pin "2") (pinfunction "2_2") (pintype "passive"))
    )
    (net (code "74") (name "Net-(D8-A-Pad3)") (class "Default")
      (node (ref "D8") (pin "3") (pinfunction "A_3") (pintype "passive"))
      (node (ref "D8") (pin "4") (pinfunction "A_4") (pintype "passive"))
      (node (ref "R11") (pin "2") (pinfunction "2_2") (pintype "passive"))
    )
    (net (code "75") (name "Net-(D9-A)") (class "Default")
      (node (ref "D9") (pin "2") (pinfunction "A_2") (pintype "passive"))
      (node (ref "R19") (pin "2") (pinfunction "2_2") (pintype "passive"))
      (node (ref "R21") (pin "1") (pinfunction "1_1") (pintype "passive"))
    )
    (net (code "76") (name "Net-(D11-A)") (class "Default")
      (node (ref "D11") (pin "1") (pinfunction "A_1") (pintype "passive"))
      (node (ref "R24") (pin "2") (pinfunction "2_2") (pintype "passive"))
    )
    (net (code "77") (name "Net-(D12-A)") (class "Default")
      (node (ref "D12") (pin "1") (pinfunction "A_1") (pintype "passive"))
      (node (ref "R25") (pin "2") (pinfunction "2_2") (pintype "passive"))
    )
    (net (code "78") (name "Net-(D13-A)") (class "Default")
      (node (ref "D13") (pin "1") (pinfunction "A_1") (pintype "passive"))
      (node (ref "R26") (pin "2") (pinfunction "2_2") (pintype "passive"))
    )
    (net (code "79") (name "Net-(D14-A)") (class "Default")
      (node (ref "D14") (pin "1") (pinfunction "A_1") (pintype "passive"))
      (node (ref "R27") (pin "2") (pinfunction "2_2") (pintype "passive"))
    )
    (net (code "80") (name "Net-(D15-A)") (class "Default")
      (node (ref "D15") (pin "1") (pinfunction "A_1") (pintype "passive"))
      (node (ref "R28") (pin "2") (pinfunction "2_2") (pintype "passive"))
    )
    (net (code "81") (name "Net-(D16-A)") (class "Default")
      (node (ref "D16") (pin "1") (pinfunction "A_1") (pintype "passive"))
      (node (ref "R29") (pin "2") (pinfunction "2_2") (pintype "passive"))
    )
    (net (code "82") (name "Net-(DX-A)") (class "Default")
      (node (ref "DX") (pin "1") (pinfunction "A_1") (pintype "passive"))
      (node (ref "R23") (pin "2") (pinfunction "2_2") (pintype "passive"))
    )
    (net (code "83") (name "Net-(U1-EN)") (class "Default")
      (node (ref "R13") (pin "2") (pinfunction "2_2") (pintype "passive"))
      (node (ref "U1") (pin "3") (pinfunction "EN_3") (pintype "input"))
    )
    (net (code "84") (name "unconnected-(IC1-SDA{slash}SMBDATA{slash}NON_REM1-Pad40)") (class "Default")
      (node (ref "IC1") (pin "40") (pinfunction "SDA/SMBDATA/NON_REM1_40") (pintype "bidirectional+no_connect"))
    )
    (net (code "85") (name "unconnected-(IC1-VDD33-Pad46)") (class "Default")
      (node (ref "IC1") (pin "46") (pinfunction "VDD33_46") (pintype "power_in+no_connect"))
    )
    (net (code "86") (name "unconnected-(IC1-VDD33CR-Pad24)") (class "Default")
      (node (ref "IC1") (pin "24") (pinfunction "VDD33CR_24") (pintype "power_in+no_connect"))
    )
    (net (code "87") (name "unconnected-(U1-NC-Pad4)") (class "Default")
      (node (ref "U1") (pin "4") (pinfunction "NC_4") (pintype "passive"))
    )
    (net (code "88") (name "unconnected-(U5-ENB-Pad4)") (class "Default")
      (node (ref "U5") (pin "4") (pinfunction "ENB_4") (pintype "input+no_connect"))
    )
    (net (code "89") (name "unconnected-(U5-OUTB-Pad5)") (class "Default")
      (node (ref "U5") (pin "5") (pinfunction "OUTB_5") (pintype "output+no_connect"))
    )
    (net (code "90") (name "unconnected-(U5-~{FLGB}-Pad3)") (class "Default")
      (node (ref "U5") (pin "3") (pinfunction "~{FLGB}_3") (pintype "open_collector+no_connect"))
    )
  )
)
